# TouScruino-avr-ui1-v0.net
KiCad netlist of a schematic drawn in EAGLE
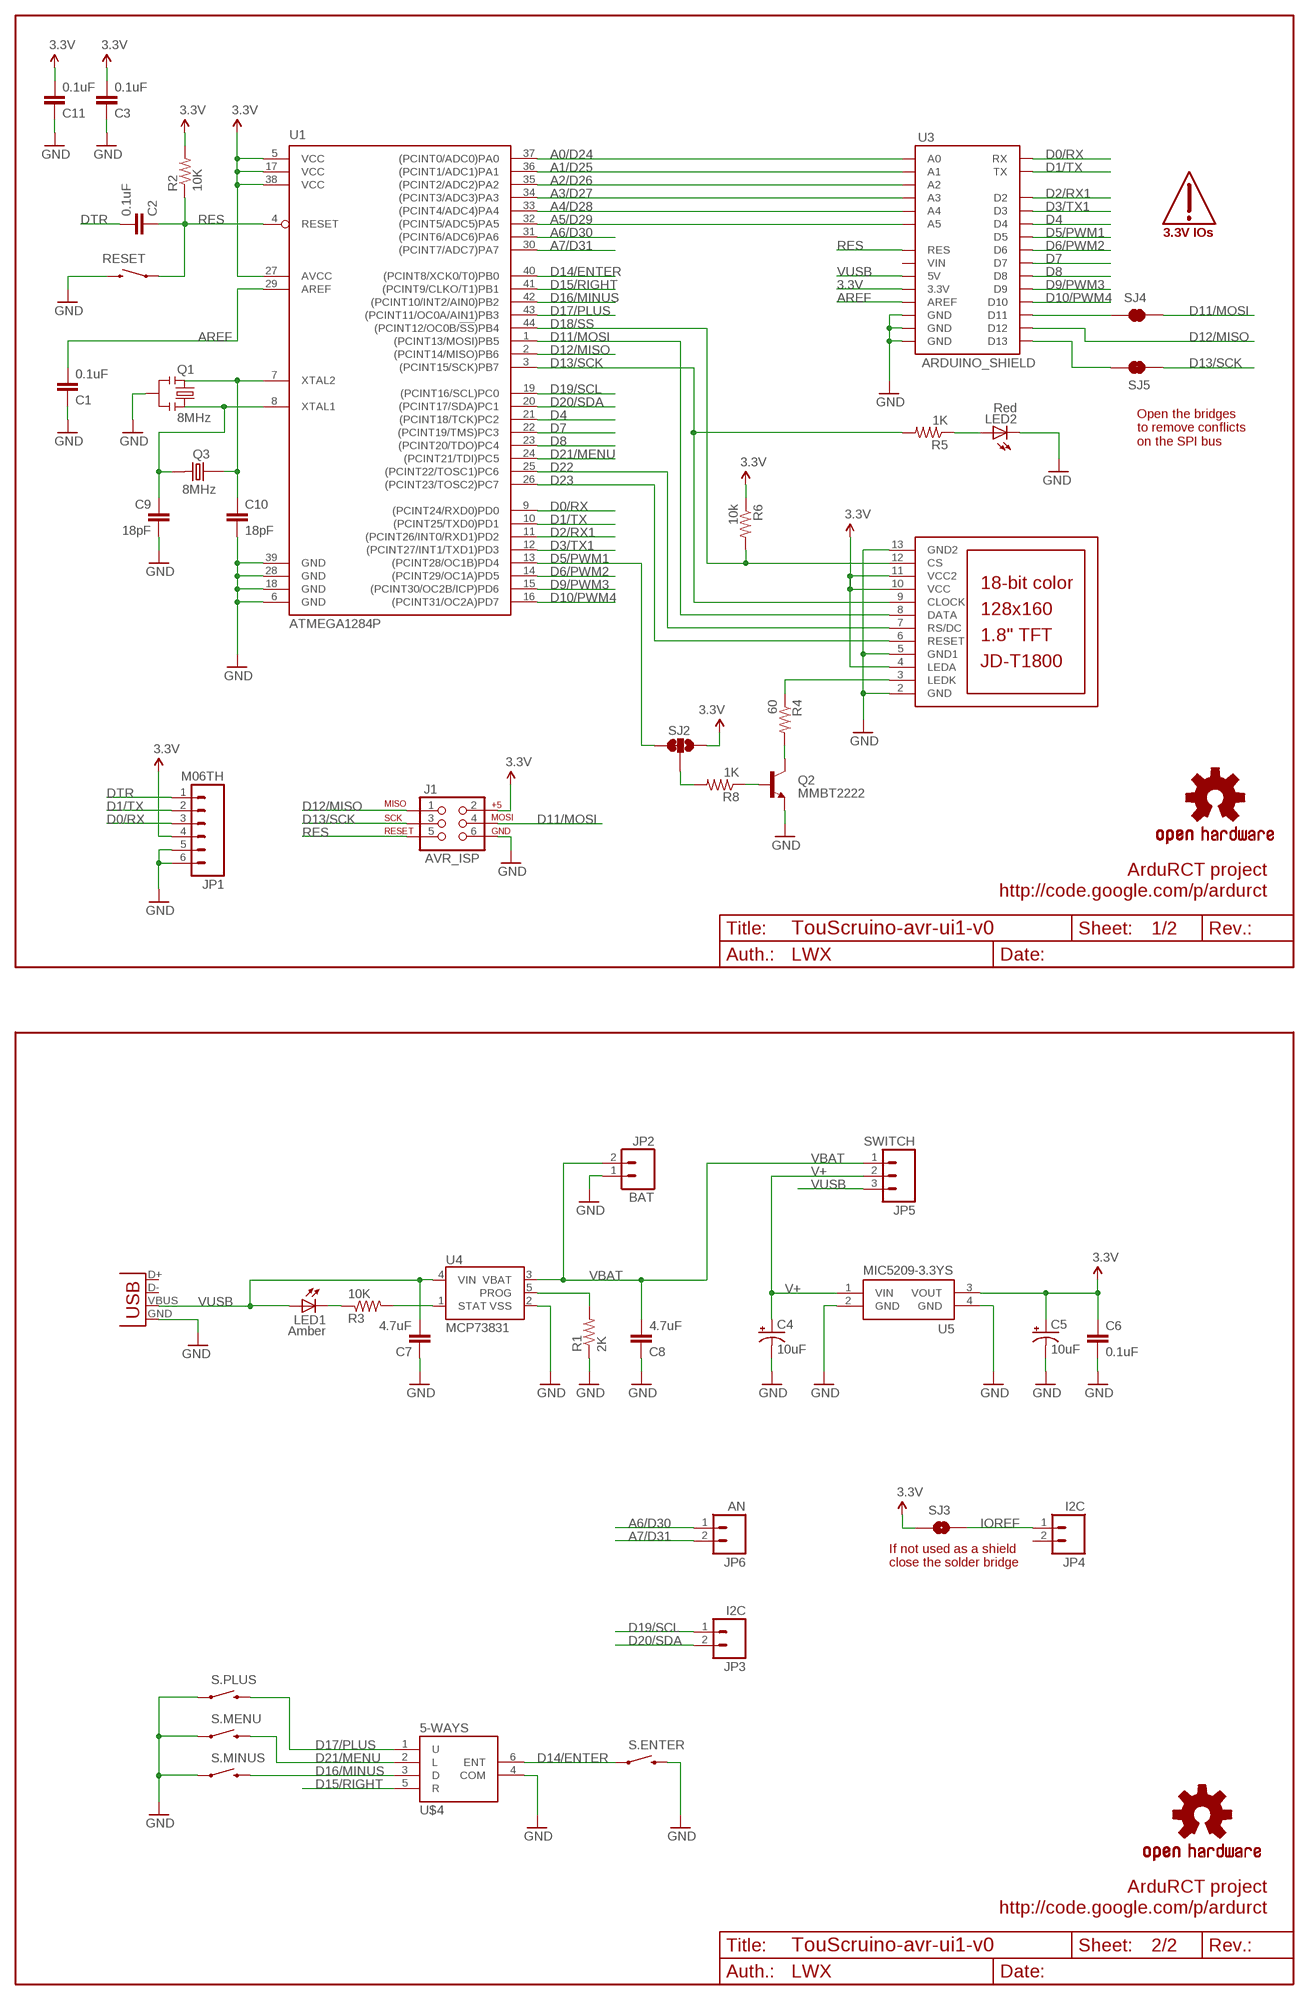
[diagram p0: schematic, sheet 1]

(export (version "E")
  (design (tool "Eeschema 10.0.6"))
  (components
    (comp (ref "C1")
      (value "0.1uF")
      (footprint "eagle-import:0805")
      (libsource (lib "eagle-import") (part "CAP0805"))
    )
    (comp (ref "C2")
      (value "0.1uF")
      (footprint "eagle-import:0805")
      (libsource (lib "eagle-import") (part "CAP0805"))
    )
    (comp (ref "C3")
      (value "0.1uF")
      (footprint "eagle-import:0805")
      (libsource (lib "eagle-import") (part "CAP0805"))
    )
    (comp (ref "C4")
      (value "10uF")
      (footprint "eagle-import:EIA3216")
      (libsource (lib "eagle-import") (part "CAP_POL1206"))
    )
    (comp (ref "C5")
      (value "10uF")
      (footprint "eagle-import:EIA3216")
      (libsource (lib "eagle-import") (part "CAP_POL1206"))
    )
    (comp (ref "C6")
      (value "0.1uF")
      (footprint "eagle-import:0805")
      (libsource (lib "eagle-import") (part "CAP0805"))
    )
    (comp (ref "C7")
      (value "4.7uF")
      (footprint "eagle-import:0805")
      (libsource (lib "eagle-import") (part "CAP0805"))
    )
    (comp (ref "C8")
      (value "4.7uF")
      (footprint "eagle-import:0805")
      (libsource (lib "eagle-import") (part "CAP0805"))
    )
    (comp (ref "C9")
      (value "18pF")
      (footprint "eagle-import:0603-CAP")
      (libsource (lib "eagle-import") (part "CAP0603-CAP"))
    )
    (comp (ref "C10")
      (value "18pF")
      (footprint "eagle-import:0603-CAP")
      (libsource (lib "eagle-import") (part "CAP0603-CAP"))
    )
    (comp (ref "C11")
      (value "0.1uF")
      (footprint "eagle-import:0805")
      (libsource (lib "eagle-import") (part "CAP0805"))
    )
    (comp (ref "J1")
      (value "AVR_ISP")
      (footprint "eagle-import:2X3")
      (libsource (lib "eagle-import") (part "AVR_SPI_PRG_6PTH"))
    )
    (comp (ref "JP1")
      (value "M06TH")
      (footprint "eagle-import:1X06")
      (libsource (lib "eagle-import") (part "M06TH"))
    )
    (comp (ref "JP2")
      (value "BAT")
      (footprint "eagle-import:JST-2-SMD")
      (libsource (lib "eagle-import") (part "M02-JST-2MM-SMT"))
    )
    (comp (ref "JP3")
      (value "I2C")
      (footprint "eagle-import:1X02")
      (libsource (lib "eagle-import") (part "M02"))
    )
    (comp (ref "JP4")
      (value "I2C")
      (footprint "eagle-import:1X02")
      (libsource (lib "eagle-import") (part "M02"))
    )
    (comp (ref "JP5")
      (value "SWITCH")
      (footprint "eagle-import:1X3_LONGPAD")
      (libsource (lib "eagle-import") (part "M03LP"))
    )
    (comp (ref "JP6")
      (value "AN")
      (footprint "eagle-import:1X02")
      (libsource (lib "eagle-import") (part "M02"))
    )
    (comp (ref "LCD1")
      (value "JD-T1800")
      (footprint "eagle-import:JD-T1800")
      (libsource (lib "eagle-import") (part "JD-T1800"))
    )
    (comp (ref "LED1")
      (value "Amber")
      (footprint "eagle-import:LED")
      (libsource (lib "eagle-import") (part "LED"))
    )
    (comp (ref "LED2")
      (value "Red")
      (footprint "eagle-import:LED")
      (libsource (lib "eagle-import") (part "LED"))
    )
    (comp (ref "Q1")
      (value "8MHz")
      (footprint "eagle-import:RESONATOR-SMD")
      (libsource (lib "eagle-import") (part "RESONATORSMD"))
    )
    (comp (ref "Q2")
      (value "MMBT2222")
      (footprint "eagle-import:SOT23-3")
      (libsource (lib "eagle-import") (part "TRANSISTOR_NPNSOT23-3"))
    )
    (comp (ref "Q3")
      (value "8MHz")
      (footprint "eagle-import:CRYSTAL_5X3.2")
      (libsource (lib "eagle-import") (part "CRYSTAL_5X3.2"))
    )
    (comp (ref "R1")
      (value "2K")
      (footprint "eagle-import:0805")
      (libsource (lib "eagle-import") (part "RESISTOR0805-RES"))
    )
    (comp (ref "R2")
      (value "10K")
      (footprint "eagle-import:0805")
      (libsource (lib "eagle-import") (part "RESISTOR0805-RES"))
    )
    (comp (ref "R3")
      (value "10K")
      (footprint "eagle-import:0805")
      (libsource (lib "eagle-import") (part "RESISTOR0805-RES"))
    )
    (comp (ref "R4")
      (value "60")
      (footprint "eagle-import:0805")
      (libsource (lib "eagle-import") (part "RESISTOR0805-RES"))
    )
    (comp (ref "R5")
      (value "1K")
      (footprint "eagle-import:0805")
      (libsource (lib "eagle-import") (part "RESISTOR0805-RES"))
    )
    (comp (ref "R6")
      (value "10k")
      (footprint "eagle-import:0805")
      (libsource (lib "eagle-import") (part "RESISTOR0805-RES"))
    )
    (comp (ref "R8")
      (value "1K")
      (footprint "eagle-import:0805")
      (libsource (lib "eagle-import") (part "RESISTOR0805-RES"))
    )
    (comp (ref "RESET")
      (value "SWITCH-MOMENTARY-2SMD")
      (footprint "eagle-import:TACTILE_SWITCH_SMD")
      (libsource (lib "eagle-import") (part "SWITCH-MOMENTARY-2SMD"))
    )
    (comp (ref "S.ENTER")
      (value "SWITCH_SMD")
      (footprint "eagle-import:TACTILE_SWITCH_SMD")
      (libsource (lib "eagle-import") (part "SWITCH_SMD"))
    )
    (comp (ref "S.MENU")
      (value "SWITCH_SMD")
      (footprint "eagle-import:TACTILE_SWITCH_SMD")
      (libsource (lib "eagle-import") (part "SWITCH_SMD"))
    )
    (comp (ref "S.MINUS")
      (value "SWITCH_SMD")
      (footprint "eagle-import:TACTILE_SWITCH_SMD")
      (libsource (lib "eagle-import") (part "SWITCH_SMD"))
    )
    (comp (ref "S.PLUS")
      (value "SWITCH_SMD")
      (footprint "eagle-import:TACTILE_SWITCH_SMD")
      (libsource (lib "eagle-import") (part "SWITCH_SMD"))
    )
    (comp (ref "SJ2")
      (value "SJ_2WAYS_1-2")
      (footprint "eagle-import:SJ_2WAYS_1-2_S")
      (libsource (lib "eagle-import") (part "SJ_2WAYS_1-2"))
    )
    (comp (ref "SJ3")
      (value "SOLDERJUMPERNO")
      (footprint "eagle-import:SJ_2S-NO")
      (libsource (lib "eagle-import") (part "SOLDERJUMPERNO"))
    )
    (comp (ref "SJ4")
      (value "SOLDERJUMPERTRACE")
      (footprint "eagle-import:SJ_2S-TRACE")
      (libsource (lib "eagle-import") (part "SOLDERJUMPERTRACE"))
    )
    (comp (ref "SJ5")
      (value "SOLDERJUMPERTRACE")
      (footprint "eagle-import:SJ_2S-TRACE")
      (libsource (lib "eagle-import") (part "SOLDERJUMPERTRACE"))
    )
    (comp (ref "U$3")
      (value "OSHW-LOGOM")
      (footprint "eagle-import:OSHW-LOGO-M")
      (libsource (lib "eagle-import") (part "OSHW-LOGOM"))
    )
    (comp (ref "U$4")
      (value "5-WAYS")
      (footprint "eagle-import:5-WAYS_ALPS")
      (libsource (lib "eagle-import") (part "5-WAYS"))
    )
    (comp (ref "U$5")
      (value "OSHW-LOGOM")
      (footprint "eagle-import:OSHW-LOGO-M")
      (libsource (lib "eagle-import") (part "OSHW-LOGOM"))
    )
    (comp (ref "U$6")
      (value "3.3V_IO")
      (footprint "eagle-import:3.3V_IO")
      (libsource (lib "eagle-import") (part "3.3V_IO"))
    )
    (comp (ref "U1")
      (value "ATMEGA1284P")
      (footprint "eagle-import:TQFP44")
      (libsource (lib "eagle-import") (part "ATMEGA324A"))
    )
    (comp (ref "U3")
      (value "ARDUINO_SHIELD")
      (footprint "eagle-import:ARDUINO_SHIELD")
      (libsource (lib "eagle-import") (part "ARDUINO_SHIELD"))
    )
    (comp (ref "U4")
      (value "MCP73831")
      (footprint "eagle-import:SOT23-5")
      (libsource (lib "eagle-import") (part "MCP73831"))
    )
    (comp (ref "U5")
      (value "MIC5209-3.3YS")
      (footprint "eagle-import:SOT223")
      (libsource (lib "eagle-import") (part "MIC5209"))
    )
    (comp (ref "X1")
      (value "USB")
      (footprint "eagle-import:USB-MICROB")
      (libsource (lib "eagle-import") (part "USB"))
    )
  )
  (nets
    (net (code "1") (name "/A0{slash}D24") (class "Default")
      (node (ref "U1") (pin "37") (pinfunction "(PCINT0/ADC0)PA0_37") (pintype "bidirectional"))
      (node (ref "U3") (pin "A0") (pinfunction "A0_A0") (pintype "bidirectional"))
    )
    (net (code "2") (name "/A1{slash}D25") (class "Default")
      (node (ref "U1") (pin "36") (pinfunction "(PCINT1/ADC1)PA1_36") (pintype "bidirectional"))
      (node (ref "U3") (pin "A1") (pinfunction "A1_A1") (pintype "bidirectional"))
    )
    (net (code "3") (name "/A2{slash}D26") (class "Default")
      (node (ref "U1") (pin "35") (pinfunction "(PCINT2/ADC2)PA2_35") (pintype "bidirectional"))
      (node (ref "U3") (pin "A2") (pinfunction "A2_A2") (pintype "bidirectional"))
    )
    (net (code "4") (name "/A3{slash}D27") (class "Default")
      (node (ref "U1") (pin "34") (pinfunction "(PCINT3/ADC3)PA3_34") (pintype "bidirectional"))
      (node (ref "U3") (pin "A3") (pinfunction "A3_A3") (pintype "bidirectional"))
    )
    (net (code "5") (name "/A4{slash}D28") (class "Default")
      (node (ref "U1") (pin "33") (pinfunction "(PCINT4/ADC4)PA4_33") (pintype "bidirectional"))
      (node (ref "U3") (pin "A4") (pinfunction "A4_A4") (pintype "bidirectional"))
    )
    (net (code "6") (name "/A5{slash}D29") (class "Default")
      (node (ref "U1") (pin "32") (pinfunction "(PCINT5/ADC5)PA5_32") (pintype "bidirectional"))
      (node (ref "U3") (pin "A5") (pinfunction "A5_A5") (pintype "bidirectional"))
    )
    (net (code "7") (name "/A6{slash}D30") (class "Default")
      (node (ref "JP6") (pin "1") (pinfunction "1_1") (pintype "passive"))
      (node (ref "U1") (pin "31") (pinfunction "(PCINT6/ADC6)PA6_31") (pintype "bidirectional"))
    )
    (net (code "8") (name "/A7{slash}D31") (class "Default")
      (node (ref "JP6") (pin "2") (pinfunction "2_2") (pintype "passive"))
      (node (ref "U1") (pin "30") (pinfunction "(PCINT7/ADC7)PA7_30") (pintype "bidirectional"))
    )
    (net (code "9") (name "/AREF") (class "Default")
      (node (ref "C1") (pin "2") (pinfunction "2_2") (pintype "passive"))
      (node (ref "U1") (pin "29") (pinfunction "AREF_29") (pintype "passive"))
      (node (ref "U3") (pin "AREF") (pinfunction "AREF_AREF") (pintype "bidirectional"))
    )
    (net (code "10") (name "/D0{slash}RX") (class "Default")
      (node (ref "JP1") (pin "3") (pinfunction "3_3") (pintype "passive"))
      (node (ref "U1") (pin "9") (pinfunction "(PCINT24/RXD0)PD0_9") (pintype "bidirectional"))
      (node (ref "U3") (pin "RX") (pinfunction "RX_RX") (pintype "bidirectional"))
    )
    (net (code "11") (name "/D1{slash}TX") (class "Default")
      (node (ref "JP1") (pin "2") (pinfunction "2_2") (pintype "passive"))
      (node (ref "U1") (pin "10") (pinfunction "(PCINT25/TXD0)PD1_10") (pintype "bidirectional"))
      (node (ref "U3") (pin "TX") (pinfunction "TX_TX") (pintype "bidirectional"))
    )
    (net (code "12") (name "/D2{slash}RX1") (class "Default")
      (node (ref "U1") (pin "11") (pinfunction "(PCINT26/INT0/RXD1)PD2_11") (pintype "bidirectional"))
      (node (ref "U3") (pin "D2") (pinfunction "D2_D2") (pintype "bidirectional"))
    )
    (net (code "13") (name "/D3{slash}TX1") (class "Default")
      (node (ref "U1") (pin "12") (pinfunction "(PCINT27/INT1/TXD1)PD3_12") (pintype "bidirectional"))
      (node (ref "U3") (pin "D3") (pinfunction "D3_D3") (pintype "bidirectional"))
    )
    (net (code "14") (name "/D4") (class "Default")
      (node (ref "U1") (pin "21") (pinfunction "(PCINT18/TCK)PC2_21") (pintype "output"))
      (node (ref "U3") (pin "D4") (pinfunction "D4_D4") (pintype "bidirectional"))
    )
    (net (code "15") (name "/D5{slash}PWM1") (class "Default")
      (node (ref "SJ2") (pin "1") (pinfunction "1_1") (pintype "passive"))
      (node (ref "U1") (pin "13") (pinfunction "(PCINT28/OC1B)PD4_13") (pintype "bidirectional"))
      (node (ref "U3") (pin "D5") (pinfunction "D5_D5") (pintype "bidirectional"))
    )
    (net (code "16") (name "/D6{slash}PWM2") (class "Default")
      (node (ref "U1") (pin "14") (pinfunction "(PCINT29/OC1A)PD5_14") (pintype "bidirectional"))
      (node (ref "U3") (pin "D6") (pinfunction "D6_D6") (pintype "bidirectional"))
    )
    (net (code "17") (name "/D7") (class "Default")
      (node (ref "U1") (pin "22") (pinfunction "(PCINT19/TMS)PC3_22") (pintype "output"))
      (node (ref "U3") (pin "D7") (pinfunction "D7_D7") (pintype "bidirectional"))
    )
    (net (code "18") (name "/D8") (class "Default")
      (node (ref "U1") (pin "23") (pinfunction "(PCINT20/TDO)PC4_23") (pintype "output"))
      (node (ref "U3") (pin "D8") (pinfunction "D8_D8") (pintype "bidirectional"))
    )
    (net (code "19") (name "/D9{slash}PWM3") (class "Default")
      (node (ref "U1") (pin "15") (pinfunction "(PCINT30/OC2B/ICP)PD6_15") (pintype "bidirectional"))
      (node (ref "U3") (pin "D9") (pinfunction "D9_D9") (pintype "bidirectional"))
    )
    (net (code "20") (name "/D10{slash}PWM4") (class "Default")
      (node (ref "U1") (pin "16") (pinfunction "(PCINT31/OC2A)PD7_16") (pintype "bidirectional"))
      (node (ref "U3") (pin "D10") (pinfunction "D10_D10") (pintype "bidirectional"))
    )
    (net (code "21") (name "/D11{slash}MOSI") (class "Default")
      (node (ref "J1") (pin "4") (pinfunction "4_4") (pintype "passive"))
      (node (ref "LCD1") (pin "8") (pinfunction "DATA_8") (pintype "bidirectional"))
      (node (ref "SJ4") (pin "2") (pinfunction "2_2") (pintype "passive"))
      (node (ref "U1") (pin "1") (pinfunction "(PCINT13/MOSI)PB5_1") (pintype "bidirectional"))
    )
    (net (code "22") (name "/D12{slash}MISO") (class "Default")
      (node (ref "J1") (pin "1") (pinfunction "1_1") (pintype "passive"))
      (node (ref "U1") (pin "2") (pinfunction "(PCINT14/MISO)PB6_2") (pintype "bidirectional"))
      (node (ref "U3") (pin "D12") (pinfunction "D12_D12") (pintype "bidirectional"))
    )
    (net (code "23") (name "/D13{slash}SCK") (class "Default")
      (node (ref "J1") (pin "3") (pinfunction "3_3") (pintype "passive"))
      (node (ref "LCD1") (pin "9") (pinfunction "CLOCK_9") (pintype "input"))
      (node (ref "R5") (pin "2") (pinfunction "2_2") (pintype "passive"))
      (node (ref "SJ5") (pin "1") (pinfunction "1_1") (pintype "passive"))
      (node (ref "U1") (pin "3") (pinfunction "(PCINT15/SCK)PB7_3") (pintype "bidirectional"))
    )
    (net (code "24") (name "/D14{slash}ENTER") (class "Default")
      (node (ref "S.ENTER") (pin "1") (pinfunction "1_1") (pintype "passive"))
      (node (ref "U$4") (pin "6") (pinfunction "ENT_6") (pintype "bidirectional"))
      (node (ref "U1") (pin "40") (pinfunction "(PCINT8/XCK0/T0)PB0_40") (pintype "bidirectional"))
    )
    (net (code "25") (name "/D15{slash}RIGHT") (class "Default")
      (node (ref "U$4") (pin "5") (pinfunction "R_5") (pintype "bidirectional"))
      (node (ref "U1") (pin "41") (pinfunction "(PCINT9/CLKO/T1)PB1_41") (pintype "bidirectional"))
    )
    (net (code "26") (name "/D16{slash}MINUS") (class "Default")
      (node (ref "S.MINUS") (pin "3") (pinfunction "2_3") (pintype "passive"))
      (node (ref "U$4") (pin "3") (pinfunction "D_3") (pintype "bidirectional"))
      (node (ref "U1") (pin "42") (pinfunction "(PCINT10/INT2/AIN0)PB2_42") (pintype "bidirectional"))
    )
    (net (code "27") (name "/D17{slash}PLUS") (class "Default")
      (node (ref "S.PLUS") (pin "3") (pinfunction "2_3") (pintype "passive"))
      (node (ref "U$4") (pin "1") (pinfunction "U_1") (pintype "bidirectional"))
      (node (ref "U1") (pin "43") (pinfunction "(PCINT11/OC0A/AIN1)PB3_43") (pintype "bidirectional"))
    )
    (net (code "28") (name "/D18{slash}SS") (class "Default")
      (node (ref "LCD1") (pin "12") (pinfunction "CS_12") (pintype "input"))
      (node (ref "R6") (pin "2") (pinfunction "2_2") (pintype "passive"))
      (node (ref "U1") (pin "44") (pinfunction "(PCINT12/OC0B/~{SS})PB4_44") (pintype "bidirectional"))
    )
    (net (code "29") (name "/D19{slash}SCL") (class "Default")
      (node (ref "JP3") (pin "1") (pinfunction "1_1") (pintype "passive"))
      (node (ref "U1") (pin "19") (pinfunction "(PCINT16/SCL)PC0_19") (pintype "output"))
    )
    (net (code "30") (name "/D20{slash}SDA") (class "Default")
      (node (ref "JP3") (pin "2") (pinfunction "2_2") (pintype "passive"))
      (node (ref "U1") (pin "20") (pinfunction "(PCINT17/SDA)PC1_20") (pintype "output"))
    )
    (net (code "31") (name "/D21{slash}MENU") (class "Default")
      (node (ref "S.MENU") (pin "3") (pinfunction "2_3") (pintype "passive"))
      (node (ref "U$4") (pin "2") (pinfunction "L_2") (pintype "bidirectional"))
      (node (ref "U1") (pin "24") (pinfunction "(PCINT21/TDI)PC5_24") (pintype "output"))
    )
    (net (code "32") (name "/D22") (class "Default")
      (node (ref "LCD1") (pin "7") (pinfunction "RS/DC_7") (pintype "input"))
      (node (ref "U1") (pin "25") (pinfunction "(PCINT22/TOSC1)PC6_25") (pintype "output"))
    )
    (net (code "33") (name "/D23") (class "Default")
      (node (ref "LCD1") (pin "6") (pinfunction "RESET_6") (pintype "input"))
      (node (ref "U1") (pin "26") (pinfunction "(PCINT23/TOSC2)PC7_26") (pintype "output"))
    )
    (net (code "34") (name "/DTR") (class "Default")
      (node (ref "C2") (pin "2") (pinfunction "2_2") (pintype "passive"))
      (node (ref "JP1") (pin "1") (pinfunction "1_1") (pintype "passive"))
    )
    (net (code "35") (name "/IOREF") (class "Default")
      (node (ref "JP4") (pin "1") (pinfunction "1_1") (pintype "passive"))
      (node (ref "SJ3") (pin "2") (pinfunction "2_2") (pintype "passive"))
    )
    (net (code "36") (name "/RES") (class "Default")
      (node (ref "C2") (pin "1") (pinfunction "1_1") (pintype "passive"))
      (node (ref "J1") (pin "5") (pinfunction "5_5") (pintype "passive"))
      (node (ref "R2") (pin "1") (pinfunction "1_1") (pintype "passive"))
      (node (ref "RESET") (pin "1") (pinfunction "1_1") (pintype "passive"))
      (node (ref "U1") (pin "4") (pinfunction "RESET_4") (pintype "input"))
      (node (ref "U3") (pin "RES") (pinfunction "RES_RES") (pintype "bidirectional"))
    )
    (net (code "37") (name "/V+") (class "Default")
      (node (ref "C4") (pin "A") (pinfunction "+_A") (pintype "passive"))
      (node (ref "JP5") (pin "2") (pinfunction "2_2") (pintype "passive"))
      (node (ref "U5") (pin "1") (pinfunction "VIN_1") (pintype "bidirectional"))
    )
    (net (code "38") (name "/VBAT") (class "Default")
      (node (ref "C8") (pin "2") (pinfunction "2_2") (pintype "passive"))
      (node (ref "JP2") (pin "2") (pinfunction "2_2") (pintype "passive"))
      (node (ref "JP5") (pin "1") (pinfunction "1_1") (pintype "passive"))
      (node (ref "U4") (pin "3") (pinfunction "VBAT_3") (pintype "power_in"))
    )
    (net (code "39") (name "/VUSB") (class "Default")
      (node (ref "C7") (pin "2") (pinfunction "2_2") (pintype "passive"))
      (node (ref "JP5") (pin "3") (pinfunction "3_3") (pintype "passive"))
      (node (ref "LED1") (pin "A1") (pinfunction "A_A1") (pintype "passive"))
      (node (ref "U3") (pin "5V") (pinfunction "5V_5V") (pintype "bidirectional"))
      (node (ref "U4") (pin "4") (pinfunction "VIN_4") (pintype "power_in"))
      (node (ref "X1") (pin "VBUS") (pinfunction "VBUS_VBUS") (pintype "bidirectional"))
    )
    (net (code "40") (name "3.3V") (class "Default")
      (node (ref "C11") (pin "2") (pinfunction "2_2") (pintype "passive"))
      (node (ref "C3") (pin "2") (pinfunction "2_2") (pintype "passive"))
      (node (ref "C5") (pin "A") (pinfunction "+_A") (pintype "passive"))
      (node (ref "C6") (pin "1") (pinfunction "1_1") (pintype "passive"))
      (node (ref "J1") (pin "2") (pinfunction "2_2") (pintype "passive"))
      (node (ref "JP1") (pin "4") (pinfunction "4_4") (pintype "passive"))
      (node (ref "LCD1") (pin "10") (pinfunction "VCC_10") (pintype "power_in"))
      (node (ref "LCD1") (pin "11") (pinfunction "VCC2_11") (pintype "power_in"))
      (node (ref "LCD1") (pin "4") (pinfunction "LEDA_4") (pintype "input"))
      (node (ref "R2") (pin "2") (pinfunction "2_2") (pintype "passive"))
      (node (ref "R6") (pin "1") (pinfunction "1_1") (pintype "passive"))
      (node (ref "SJ2") (pin "3") (pinfunction "3_3") (pintype "passive"))
      (node (ref "SJ3") (pin "1") (pinfunction "1_1") (pintype "passive"))
      (node (ref "U1") (pin "17") (pinfunction "VCC_17") (pintype "power_in"))
      (node (ref "U1") (pin "27") (pinfunction "AVCC_27") (pintype "power_in"))
      (node (ref "U1") (pin "38") (pinfunction "VCC_38") (pintype "power_in"))
      (node (ref "U1") (pin "5") (pinfunction "VCC_5") (pintype "power_in"))
      (node (ref "U3") (pin "3.3V") (pinfunction "3.3V_3.3V") (pintype "bidirectional"))
      (node (ref "U5") (pin "3") (pinfunction "VOUT_3") (pintype "bidirectional"))
    )
    (net (code "41") (name "GND") (class "Default")
      (node (ref "C1") (pin "1") (pinfunction "1_1") (pintype "passive"))
      (node (ref "C10") (pin "2") (pinfunction "2_2") (pintype "passive"))
      (node (ref "C11") (pin "1") (pinfunction "1_1") (pintype "passive"))
      (node (ref "C3") (pin "1") (pinfunction "1_1") (pintype "passive"))
      (node (ref "C4") (pin "C") (pinfunction "-_C") (pintype "passive"))
      (node (ref "C5") (pin "C") (pinfunction "-_C") (pintype "passive"))
      (node (ref "C6") (pin "2") (pinfunction "2_2") (pintype "passive"))
      (node (ref "C7") (pin "1") (pinfunction "1_1") (pintype "passive"))
      (node (ref "C8") (pin "1") (pinfunction "1_1") (pintype "passive"))
      (node (ref "C9") (pin "2") (pinfunction "2_2") (pintype "passive"))
      (node (ref "J1") (pin "6") (pinfunction "6_6") (pintype "passive"))
      (node (ref "JP1") (pin "5") (pinfunction "5_5") (pintype "passive"))
      (node (ref "JP1") (pin "6") (pinfunction "6_6") (pintype "passive"))
      (node (ref "JP2") (pin "1") (pinfunction "1_1") (pintype "passive"))
      (node (ref "LCD1") (pin "13") (pinfunction "GND2_13") (pintype "power_in"))
      (node (ref "LCD1") (pin "2") (pinfunction "GND_2") (pintype "power_in"))
      (node (ref "LCD1") (pin "5") (pinfunction "GND1_5") (pintype "power_in"))
      (node (ref "LED2") (pin "C1") (pinfunction "C_C1") (pintype "passive"))
      (node (ref "Q1") (pin "2") (pinfunction "2_2") (pintype "passive"))
      (node (ref "Q2") (pin "2") (pinfunction "E_2") (pintype "passive"))
      (node (ref "R1") (pin "1") (pinfunction "1_1") (pintype "passive"))
      (node (ref "RESET") (pin "3") (pinfunction "2_3") (pintype "passive"))
      (node (ref "S.ENTER") (pin "3") (pinfunction "2_3") (pintype "passive"))
      (node (ref "S.MENU") (pin "1") (pinfunction "1_1") (pintype "passive"))
      (node (ref "S.MINUS") (pin "1") (pinfunction "1_1") (pintype "passive"))
      (node (ref "S.PLUS") (pin "1") (pinfunction "1_1") (pintype "passive"))
      (node (ref "U$4") (pin "4") (pinfunction "COM_4") (pintype "bidirectional"))
      (node (ref "U1") (pin "18") (pinfunction "GND_18") (pintype "power_in"))
      (node (ref "U1") (pin "28") (pinfunction "GND_28") (pintype "power_in"))
      (node (ref "U1") (pin "39") (pinfunction "GND_39") (pintype "power_in"))
      (node (ref "U1") (pin "6") (pinfunction "GND_6") (pintype "power_in"))
      (node (ref "U3") (pin "GND@0") (pinfunction "GND_GND@0") (pintype "bidirectional"))
      (node (ref "U3") (pin "GND@1") (pinfunction "GND_GND@1") (pintype "bidirectional"))
      (node (ref "U3") (pin "GND@2") (pinfunction "GND_GND@2") (pintype "bidirectional"))
      (node (ref "U4") (pin "2") (pinfunction "VSS_2") (pintype "power_in"))
      (node (ref "U5") (pin "2") (pinfunction "GND_2") (pintype "bidirectional"))
      (node (ref "U5") (pin "4") (pinfunction "GND_4") (pintype "bidirectional"))
      (node (ref "X1") (pin "GND") (pinfunction "GND_GND") (pintype "bidirectional"))
    )
    (net (code "42") (name "Net-(LCD1-LEDK)") (class "Default")
      (node (ref "LCD1") (pin "3") (pinfunction "LEDK_3") (pintype "input"))
      (node (ref "R4") (pin "1") (pinfunction "1_1") (pintype "passive"))
    )
    (net (code "43") (name "Net-(LED1-C)") (class "Default")
      (node (ref "LED1") (pin "C1") (pinfunction "C_C1") (pintype "passive"))
      (node (ref "R3") (pin "1") (pinfunction "1_1") (pintype "passive"))
    )
    (net (code "44") (name "Net-(LED2-A)") (class "Default")
      (node (ref "LED2") (pin "A1") (pinfunction "A_A1") (pintype "passive"))
      (node (ref "R5") (pin "1") (pinfunction "1_1") (pintype "passive"))
    )
    (net (code "45") (name "Net-(Q2-B)") (class "Default")
      (node (ref "Q2") (pin "1") (pinfunction "B_1") (pintype "passive"))
      (node (ref "R8") (pin "1") (pinfunction "1_1") (pintype "passive"))
    )
    (net (code "46") (name "Net-(Q2-C)") (class "Default")
      (node (ref "Q2") (pin "3") (pinfunction "C_3") (pintype "passive"))
      (node (ref "R4") (pin "2") (pinfunction "2_2") (pintype "passive"))
    )
    (net (code "47") (name "Net-(R8-Pad2)") (class "Default")
      (node (ref "R8") (pin "2") (pinfunction "2_2") (pintype "passive"))
      (node (ref "SJ2") (pin "2") (pinfunction "2_2") (pintype "passive"))
    )
    (net (code "48") (name "Net-(SJ4-Pad1)") (class "Default")
      (node (ref "SJ4") (pin "1") (pinfunction "1_1") (pintype "passive"))
      (node (ref "U3") (pin "D11") (pinfunction "D11_D11") (pintype "bidirectional"))
    )
    (net (code "49") (name "Net-(SJ5-Pad2)") (class "Default")
      (node (ref "SJ5") (pin "2") (pinfunction "2_2") (pintype "passive"))
      (node (ref "U3") (pin "D13") (pinfunction "D13_D13") (pintype "bidirectional"))
    )
    (net (code "50") (name "Net-(U1-XTAL1)") (class "Default")
      (node (ref "C9") (pin "1") (pinfunction "1_1") (pintype "passive"))
      (node (ref "Q1") (pin "1") (pinfunction "1_1") (pintype "passive"))
      (node (ref "Q3") (pin "2") (pinfunction "2_2") (pintype "passive"))
      (node (ref "U1") (pin "8") (pinfunction "XTAL1_8") (pintype "bidirectional"))
    )
    (net (code "51") (name "Net-(U1-XTAL2)") (class "Default")
      (node (ref "C10") (pin "1") (pinfunction "1_1") (pintype "passive"))
      (node (ref "Q1") (pin "3") (pinfunction "3_3") (pintype "passive"))
      (node (ref "Q3") (pin "1") (pinfunction "1_1") (pintype "passive"))
      (node (ref "U1") (pin "7") (pinfunction "XTAL2_7") (pintype "bidirectional"))
    )
    (net (code "52") (name "Net-(U4-PROG)") (class "Default")
      (node (ref "R1") (pin "2") (pinfunction "2_2") (pintype "passive"))
      (node (ref "U4") (pin "5") (pinfunction "PROG_5") (pintype "input"))
    )
    (net (code "53") (name "Net-(U4-STAT)") (class "Default")
      (node (ref "R3") (pin "2") (pinfunction "2_2") (pintype "passive"))
      (node (ref "U4") (pin "1") (pinfunction "STAT_1") (pintype "output"))
    )
    (net (code "54") (name "unconnected-(JP4-Pad2)") (class "Default")
      (node (ref "JP4") (pin "2") (pinfunction "2_2") (pintype "passive"))
    )
    (net (code "55") (name "unconnected-(U3-PadVIN)") (class "Default")
      (node (ref "U3") (pin "VIN") (pinfunction "VIN_VIN") (pintype "bidirectional"))
    )
    (net (code "56") (name "unconnected-(X1-PadD+)") (class "Default")
      (node (ref "X1") (pin "D+") (pinfunction "D+_D+") (pintype "bidirectional"))
    )
    (net (code "57") (name "unconnected-(X1-PadD-)") (class "Default")
      (node (ref "X1") (pin "D-") (pinfunction "D-_D-") (pintype "bidirectional"))
    )
  )
)
